# Sheet1.net
KiCad netlist of a schematic drawn in Altium Designer
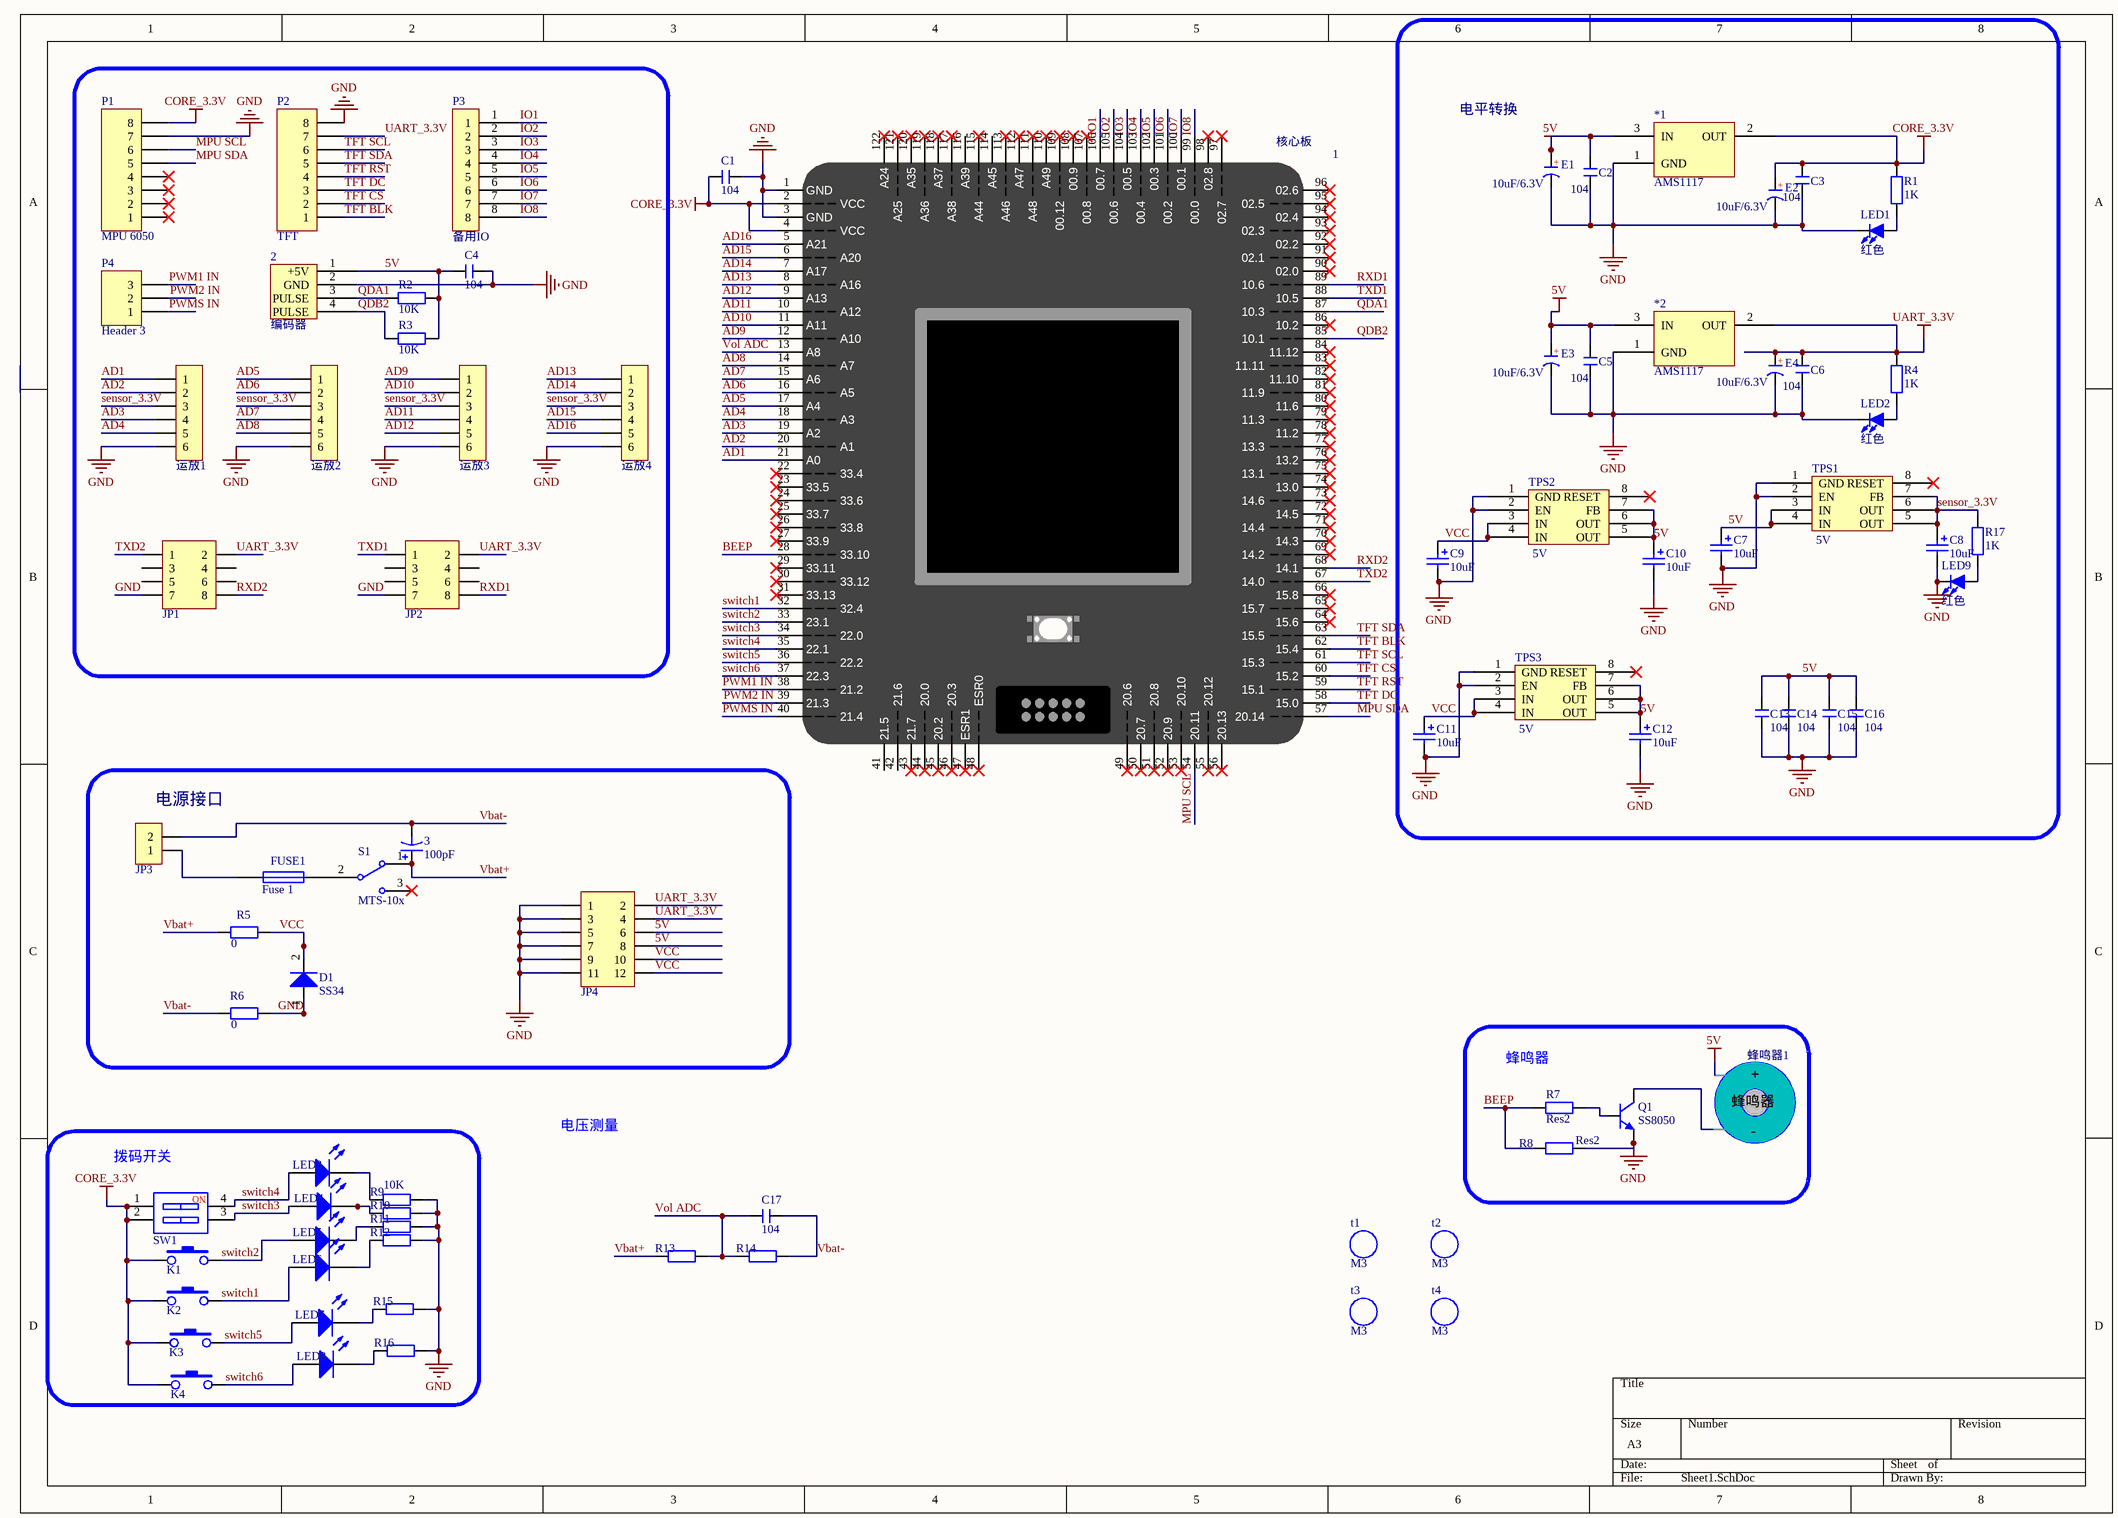
[diagram p0: Sheet1.SchDoc]

(export (version "E")
  (design (tool "Eeschema 10.0.6"))
  (components
    (comp (ref "*1") (value "AMS1117") (footprint "SOT223_M") (libsource (lib "Schlib1") (part "AMS1117")))
    (comp (ref "*2") (value "AMS1117") (footprint "SOT223_M") (libsource (lib "Schlib1") (part "AMS1117")))
    (comp (ref "1") (value "核心板") (footprint "TC264_CoreBoard") (libsource (lib "核心板") (part "Component_1")))
    (comp (ref "2") (value "编码器") (footprint "HDR1X4") (libsource (lib "我的元件库") (part "光电码盘")))
    (comp (ref "3")
      (value "100pF")
      (footprint "CAP 5.0*10*20 - BK")
      (description "Polarized Capacitor (Surface Mount)")
      (fields (field (name "Comment") "Cap Pol3") (field (name "PUBLISHER") "Altium Limited"))
      (libsource (lib "Miscellaneous Devices") (part "Cap Pol3"))
    )
    (comp (ref "C1")
      (value "104")
      (footprint "C 0603_M")
      (description "无极性贴片电容")
      (fields (field (name "版权归属") "源创客"))
      (libsource (lib "3.1   - 电阻-电容-电感") (part "C"))
    )
    (comp (ref "C2")
      (value "104")
      (footprint "C 0603_M")
      (description "无极性贴片电容")
      (fields (field (name "版权归属") "源创客"))
      (libsource (lib "3.1   - 电阻-电容-电感") (part "C"))
    )
    (comp (ref "C3")
      (value "104")
      (footprint "C 0603_M")
      (description "无极性贴片电容")
      (fields (field (name "版权归属") "源创客"))
      (libsource (lib "3.1   - 电阻-电容-电感") (part "C"))
    )
    (comp (ref "C4")
      (value "104")
      (footprint "C 0603_M")
      (description "无极性贴片电容")
      (fields (field (name "版权归属") "源创客"))
      (libsource (lib "3.1   - 电阻-电容-电感") (part "C"))
    )
    (comp (ref "C5")
      (value "104")
      (footprint "C 0603_M")
      (description "无极性贴片电容")
      (fields (field (name "版权归属") "源创客"))
      (libsource (lib "3.1   - 电阻-电容-电感") (part "C"))
    )
    (comp (ref "C6")
      (value "104")
      (footprint "C 0603_M")
      (description "无极性贴片电容")
      (fields (field (name "版权归属") "源创客"))
      (libsource (lib "3.1   - 电阻-电容-电感") (part "C"))
    )
    (comp (ref "C7")
      (value "10uF")
      (footprint "C3216")
      (description "Polarized Capacitor (Radial)")
      (fields (field (name "Comment") "10uf") (field (name "PUBLISHER") "Altium Limited"))
      (libsource (lib "SYUCT2018_2") (part "Cap Pol1"))
    )
    (comp (ref "C8")
      (value "10uF")
      (footprint "C3216")
      (description "Polarized Capacitor (Radial)")
      (fields (field (name "Comment") "10uf") (field (name "PUBLISHER") "Altium Limited"))
      (libsource (lib "SYUCT2018_2") (part "Cap Pol1"))
    )
    (comp (ref "C9")
      (value "10uF")
      (footprint "C3216")
      (description "Polarized Capacitor (Radial)")
      (fields (field (name "Comment") "10uf") (field (name "PUBLISHER") "Altium Limited"))
      (libsource (lib "SYUCT2018_2") (part "Cap Pol1"))
    )
    (comp (ref "C10")
      (value "10uF")
      (footprint "C3216")
      (description "Polarized Capacitor (Radial)")
      (fields (field (name "Comment") "10uf") (field (name "PUBLISHER") "Altium Limited"))
      (libsource (lib "SYUCT2018_2") (part "Cap Pol1"))
    )
    (comp (ref "C11")
      (value "10uF")
      (footprint "C3216")
      (description "Polarized Capacitor (Radial)")
      (fields (field (name "Comment") "10uf") (field (name "PUBLISHER") "Altium Limited"))
      (libsource (lib "SYUCT2018_2") (part "Cap Pol1"))
    )
    (comp (ref "C12")
      (value "10uF")
      (footprint "C3216")
      (description "Polarized Capacitor (Radial)")
      (fields (field (name "Comment") "10uf") (field (name "PUBLISHER") "Altium Limited"))
      (libsource (lib "SYUCT2018_2") (part "Cap Pol1"))
    )
    (comp (ref "C13")
      (value "104")
      (footprint "C 0603_M")
      (description "无极性贴片电容")
      (fields (field (name "版权归属") "源创客"))
      (libsource (lib "3.1   - 电阻-电容-电感") (part "C"))
    )
    (comp (ref "C14")
      (value "104")
      (footprint "C 0603_M")
      (description "无极性贴片电容")
      (fields (field (name "版权归属") "源创客"))
      (libsource (lib "3.1   - 电阻-电容-电感") (part "C"))
    )
    (comp (ref "C15")
      (value "104")
      (footprint "C 0603_M")
      (description "无极性贴片电容")
      (fields (field (name "版权归属") "源创客"))
      (libsource (lib "3.1   - 电阻-电容-电感") (part "C"))
    )
    (comp (ref "C16")
      (value "104")
      (footprint "C 0603_M")
      (description "无极性贴片电容")
      (fields (field (name "版权归属") "源创客"))
      (libsource (lib "3.1   - 电阻-电容-电感") (part "C"))
    )
    (comp (ref "C17")
      (value "104")
      (footprint "C 0603_M")
      (description "无极性贴片电容")
      (fields (field (name "版权归属") "源创客"))
      (libsource (lib "3.1   - 电阻-电容-电感") (part "C"))
    )
    (comp (ref "D1")
      (value "SS34")
      (footprint "SMA")
      (description "High Conductance Fast Diode")
      (fields (field (name "PUBLISHER") "Altium Limited"))
      (libsource (lib "Miscellaneous Devices") (part "Diode 1N4148"))
    )
    (comp (ref "E1")
      (value "10uF/6.3V")
      (footprint "CD A(3216)")
      (description "贴片钽电容")
      (fields (field (name "版权归属") "源创客"))
      (libsource (lib "3.1   - 电阻-电容-电感") (part "C-CD"))
    )
    (comp (ref "E2")
      (value "10uF/6.3V")
      (footprint "CD A(3216)")
      (description "贴片钽电容")
      (fields (field (name "版权归属") "源创客"))
      (libsource (lib "3.1   - 电阻-电容-电感") (part "C-CD"))
    )
    (comp (ref "E3")
      (value "10uF/6.3V")
      (footprint "CD A(3216)")
      (description "贴片钽电容")
      (fields (field (name "版权归属") "源创客"))
      (libsource (lib "3.1   - 电阻-电容-电感") (part "C-CD"))
    )
    (comp (ref "E4")
      (value "10uF/6.3V")
      (footprint "CD A(3216)")
      (description "贴片钽电容")
      (fields (field (name "版权归属") "源创客"))
      (libsource (lib "3.1   - 电阻-电容-电感") (part "C-CD"))
    )
    (comp (ref "FUSE1")
      (value "Fuse 1")
      (footprint "FU 0805")
      (description "Fuse")
      (fields (field (name "PUBLISHER") "Altium Limited"))
      (libsource (lib "Miscellaneous Devices") (part "Fuse 1"))
    )
    (comp (ref "JP1")
      (value "Header 4X2")
      (footprint "HDR2.54-LI-2x4P")
      (description "4*2P接插件")
      (fields (field (name "版权归属") "源创客"))
      (libsource (lib "4.5   - 接插件-脚距2.54") (part "Header 4X2"))
    )
    (comp (ref "JP2")
      (value "Header 4X2")
      (footprint "HDR2.54-LI-2x4P")
      (description "4*2P接插件")
      (fields (field (name "版权归属") "源创客"))
      (libsource (lib "4.5   - 接插件-脚距2.54") (part "Header 4X2"))
    )
    (comp (ref "JP3")
      (value "HDR-1X2")
      (footprint "KF301-5.0-2P")
      (description "2P接插件")
      (fields (field (name "版权归属") "源创客"))
      (libsource (lib "4.9   - 接插件-脚距5.0") (part "Header 2"))
    )
    (comp (ref "JP4")
      (value "Header 6X2")
      (footprint "HDR2.54-LI-2x6P")
      (description "6*2P接插件")
      (fields (field (name "版权归属") "源创客"))
      (libsource (lib "4.5   - 接插件-脚距2.54") (part "Header  6X2"))
    )
    (comp (ref "K1")
      (value "K2")
      (footprint "KEY-SMD1")
      (description "按键")
      (libsource (lib "PCB_Project-1.0") (part "KEY_1"))
    )
    (comp (ref "K2")
      (value "K2")
      (footprint "KEY-SMD1")
      (description "按键")
      (libsource (lib "PCB_Project-1.0") (part "KEY_1"))
    )
    (comp (ref "K3")
      (value "K2")
      (footprint "KEY-SMD1")
      (description "按键")
      (libsource (lib "PCB_Project-1.0") (part "KEY_1"))
    )
    (comp (ref "K4")
      (value "K2")
      (footprint "KEY-SMD1")
      (description "按键")
      (libsource (lib "PCB_Project-1.0") (part "KEY_1"))
    )
    (comp (ref "LED1")
      (value "红色")
      (footprint "LED 0805B")
      (description "贴片LED")
      (fields (field (name "版权归属") "源创客"))
      (libsource (lib "9.1   - LED") (part "LED-SMD"))
    )
    (comp (ref "LED2")
      (value "红色")
      (footprint "LED 0805B")
      (description "贴片LED")
      (fields (field (name "版权归属") "源创客"))
      (libsource (lib "9.1   - LED") (part "LED-SMD"))
    )
    (comp (ref "LED3")
      (value "LED4")
      (footprint "LED 0805B")
      (description "Typical RED, GREEN, YELLOW, AMBER GaAs LED")
      (fields (field (name "PUBLISHER") "Altium Limited"))
      (libsource (lib "SYUCT2018_1") (part "LED2"))
    )
    (comp (ref "LED4")
      (value "LED4")
      (footprint "LED 0805B")
      (description "Typical RED, GREEN, YELLOW, AMBER GaAs LED")
      (fields (field (name "PUBLISHER") "Altium Limited"))
      (libsource (lib "SYUCT2018_1") (part "LED2"))
    )
    (comp (ref "LED5")
      (value "LED4")
      (footprint "LED 0805B")
      (description "Typical RED, GREEN, YELLOW, AMBER GaAs LED")
      (fields (field (name "PUBLISHER") "Altium Limited"))
      (libsource (lib "SYUCT2018_1") (part "LED2"))
    )
    (comp (ref "LED6")
      (value "LED4")
      (footprint "LED 0805B")
      (description "Typical RED, GREEN, YELLOW, AMBER GaAs LED")
      (fields (field (name "PUBLISHER") "Altium Limited"))
      (libsource (lib "SYUCT2018_1") (part "LED2"))
    )
    (comp (ref "LED7")
      (value "LED4")
      (footprint "LED 0805B")
      (description "Typical RED, GREEN, YELLOW, AMBER GaAs LED")
      (fields (field (name "PUBLISHER") "Altium Limited"))
      (libsource (lib "SYUCT2018_1") (part "LED2"))
    )
    (comp (ref "LED8")
      (value "LED4")
      (footprint "LED 0805B")
      (description "Typical RED, GREEN, YELLOW, AMBER GaAs LED")
      (fields (field (name "PUBLISHER") "Altium Limited"))
      (libsource (lib "SYUCT2018_1") (part "LED2"))
    )
    (comp (ref "LED9")
      (value "红色")
      (footprint "LED 0805B")
      (description "贴片LED")
      (fields (field (name "版权归属") "源创客"))
      (libsource (lib "9.1   - LED") (part "LED-SMD"))
    )
    (comp (ref "P1")
      (value "MPU 6050")
      (footprint "HDR1X8")
      (description "Header, 8-Pin")
      (fields (field (name "PUBLISHER") "Altium Limited"))
      (libsource (lib "Miscellaneous Connectors") (part "Header 8"))
    )
    (comp (ref "P2")
      (value "TFT")
      (footprint "HDR1X8")
      (description "Header, 8-Pin")
      (fields (field (name "PUBLISHER") "Altium Limited"))
      (libsource (lib "Miscellaneous Connectors") (part "Header 8"))
    )
    (comp (ref "P3") (value "备用IO") (footprint "HDR1X8") (libsource (lib "Schlib1") (part "备用IO")))
    (comp (ref "P4")
      (value "Header 3")
      (footprint "HDR1X3")
      (description "Header, 3-Pin")
      (fields (field (name "PUBLISHER") "Altium Limited"))
      (libsource (lib "Miscellaneous Connectors") (part "Header 3"))
    )
    (comp (ref "Q1")
      (value "SS8050")
      (footprint "SOT23-3N")
      (description "高频放大-NPN型")
      (fields (field (name "版权归属") "源创客"))
      (libsource (lib "6.2   - 三极管") (part "8050-SMD"))
    )
    (comp (ref "R1")
      (value "1K")
      (footprint "R0805")
      (description "贴片电阻")
      (fields (field (name "版权归属") "源创客"))
      (libsource (lib "3.1   - 电阻-电容-电感") (part "R"))
    )
    (comp (ref "R2") (value "10K") (footprint "R0805") (libsource (lib "") (part "RES_MD_1")))
    (comp (ref "R3") (value "10K") (footprint "R0805") (libsource (lib "") (part "RES_MD_2")))
    (comp (ref "R4")
      (value "1K")
      (footprint "R0805")
      (description "贴片电阻")
      (fields (field (name "版权归属") "源创客"))
      (libsource (lib "3.1   - 电阻-电容-电感") (part "R"))
    )
    (comp (ref "R5") (value "0") (footprint "R1210") (libsource (lib "MD_分立元件自定义标准库") (part "RES_MD")))
    (comp (ref "R6") (value "0") (footprint "R1210") (libsource (lib "MD_分立元件自定义标准库") (part "RES_MD")))
    (comp (ref "R7")
      (value "Res2")
      (footprint "R0805")
      (description "Resistor")
      (fields (field (name "PUBLISHER") "Altium Limited"))
      (libsource (lib "") (part "Res2_1"))
    )
    (comp (ref "R8")
      (value "Res2")
      (footprint "R0805")
      (description "Resistor")
      (fields (field (name "PUBLISHER") "Altium Limited"))
      (libsource (lib "Miscellaneous Devices") (part "Res2"))
    )
    (comp (ref "R9")
      (value "10K")
      (footprint "R0805")
      (description "Resistor")
      (fields (field (name "PUBLISHER") "Altium Limited"))
      (libsource (lib "我的元件库") (part "电阻"))
    )
    (comp (ref "R10")
      (value "10K")
      (footprint "R0805")
      (description "Resistor")
      (fields (field (name "PUBLISHER") "Altium Limited"))
      (libsource (lib "我的元件库") (part "电阻"))
    )
    (comp (ref "R11")
      (value "10K")
      (footprint "R0805")
      (description "Resistor")
      (fields (field (name "PUBLISHER") "Altium Limited"))
      (libsource (lib "我的元件库") (part "电阻"))
    )
    (comp (ref "R12")
      (value "10K")
      (footprint "R0805")
      (description "Resistor")
      (fields (field (name "PUBLISHER") "Altium Limited"))
      (libsource (lib "我的元件库") (part "电阻"))
    )
    (comp (ref "R13")
      (value "10K")
      (footprint "R0805")
      (description "Resistor")
      (fields (field (name "PUBLISHER") "Altium Limited"))
      (libsource (lib "我的元件库") (part "电阻"))
    )
    (comp (ref "R14")
      (value "10K")
      (footprint "R0805")
      (description "Resistor")
      (fields (field (name "PUBLISHER") "Altium Limited"))
      (libsource (lib "我的元件库") (part "电阻"))
    )
    (comp (ref "R15")
      (value "10K")
      (footprint "R0805")
      (description "Resistor")
      (fields (field (name "PUBLISHER") "Altium Limited"))
      (libsource (lib "我的元件库") (part "电阻"))
    )
    (comp (ref "R16")
      (value "10K")
      (footprint "R0805")
      (description "Resistor")
      (fields (field (name "PUBLISHER") "Altium Limited"))
      (libsource (lib "我的元件库") (part "电阻"))
    )
    (comp (ref "R17")
      (value "1K")
      (footprint "R0805")
      (description "贴片电阻")
      (fields (field (name "版权归属") "源创客"))
      (libsource (lib "3.1   - 电阻-电容-电感") (part "R"))
    )
    (comp (ref "S1")
      (value "MTS-10x")
      (footprint "MTS-10x")
      (description "MTS10x系列3脚扭子开关")
      (fields (field (name "版权归属") "源创客"))
      (libsource (lib "5.1   - 按键-开关") (part "MTS-10x"))
    )
    (comp (ref "SW1")
      (value "CSW-2P")
      (footprint "CSW DIP-2P_G")
      (description "2路编码开关")
      (fields (field (name "版权归属") "源创客"))
      (libsource (lib "PCB_Project-1.0") (part "CSW-2P"))
    )
    (comp (ref "t1")
      (value "M3")
      (footprint "M3 125X200")
      (description "铜柱孔")
      (fields (field (name "版权归属") "源创客"))
      (libsource (lib "15.1 - 未分类器件") (part "M3"))
    )
    (comp (ref "t2")
      (value "M3")
      (footprint "M3 125X200")
      (description "铜柱孔")
      (fields (field (name "版权归属") "源创客"))
      (libsource (lib "15.1 - 未分类器件") (part "M3"))
    )
    (comp (ref "t3")
      (value "M3")
      (footprint "M3 125X200")
      (description "铜柱孔")
      (fields (field (name "版权归属") "源创客"))
      (libsource (lib "15.1 - 未分类器件") (part "M3"))
    )
    (comp (ref "t4")
      (value "M3")
      (footprint "M3 125X200")
      (description "铜柱孔")
      (fields (field (name "版权归属") "源创客"))
      (libsource (lib "15.1 - 未分类器件") (part "M3"))
    )
    (comp (ref "TPS1") (value "5V") (footprint "SO-8N") (libsource (lib "我的元件库") (part "TPS7350")))
    (comp (ref "TPS2") (value "5V") (footprint "SO-8N") (libsource (lib "我的元件库") (part "TPS7350")))
    (comp (ref "TPS3") (value "5V") (footprint "SO-8N") (libsource (lib "我的元件库") (part "TPS7350")))
    (comp (ref "蜂鸣器1") (value "蜂鸣器") (footprint "BELL 7.6mm") (libsource (lib "原理图") (part "蜂鸣器")))
    (comp (ref "运放1")
      (value "HDR-1X6")
      (footprint "XH2.54-LI-6P")
      (description "6P接插件")
      (libsource (lib "5.1 - 接插件-脚距1.27") (part "Header 6"))
    )
    (comp (ref "运放2")
      (value "HDR-1X6")
      (footprint "XH2.54-LI-6P")
      (description "6P接插件")
      (libsource (lib "5.1 - 接插件-脚距1.27") (part "Header 6"))
    )
    (comp (ref "运放3")
      (value "HDR-1X6")
      (footprint "XH2.54-LI-6P")
      (description "6P接插件")
      (libsource (lib "5.1 - 接插件-脚距1.27") (part "Header 6"))
    )
    (comp (ref "运放4")
      (value "HDR-1X6")
      (footprint "XH2.54-LI-6P")
      (description "6P接插件")
      (libsource (lib "5.1 - 接插件-脚距1.27") (part "Header 6"))
    )
  )
  (nets
    (net (code "1") (name "/AD1") (class "Default")
      (node (ref "1") (pin "21") (pinfunction "A0_21") (pintype "passive"))
      (node (ref "运放1") (pin "1") (pinfunction "1_1") (pintype "passive"))
    )
    (net (code "2") (name "/AD2") (class "Default")
      (node (ref "1") (pin "20") (pinfunction "A1_20") (pintype "passive"))
      (node (ref "运放1") (pin "2") (pinfunction "2_2") (pintype "passive"))
    )
    (net (code "3") (name "/AD3") (class "Default")
      (node (ref "1") (pin "19") (pinfunction "A2_19") (pintype "passive"))
      (node (ref "运放1") (pin "4") (pinfunction "4_4") (pintype "passive"))
    )
    (net (code "4") (name "/AD4") (class "Default")
      (node (ref "1") (pin "18") (pinfunction "A3_18") (pintype "passive"))
      (node (ref "运放1") (pin "5") (pinfunction "5_5") (pintype "passive"))
    )
    (net (code "5") (name "/AD5") (class "Default")
      (node (ref "1") (pin "17") (pinfunction "A4_17") (pintype "passive"))
      (node (ref "运放2") (pin "1") (pinfunction "1_1") (pintype "passive"))
    )
    (net (code "6") (name "/AD6") (class "Default")
      (node (ref "1") (pin "16") (pinfunction "A5_16") (pintype "passive"))
      (node (ref "运放2") (pin "2") (pinfunction "2_2") (pintype "passive"))
    )
    (net (code "7") (name "/AD7") (class "Default")
      (node (ref "1") (pin "15") (pinfunction "A6_15") (pintype "passive"))
      (node (ref "运放2") (pin "4") (pinfunction "4_4") (pintype "passive"))
    )
    (net (code "8") (name "/AD8") (class "Default")
      (node (ref "1") (pin "14") (pinfunction "A7_14") (pintype "passive"))
      (node (ref "运放2") (pin "5") (pinfunction "5_5") (pintype "passive"))
    )
    (net (code "9") (name "/AD9") (class "Default")
      (node (ref "1") (pin "12") (pinfunction "A10_12") (pintype "passive"))
      (node (ref "运放3") (pin "1") (pinfunction "1_1") (pintype "passive"))
    )
    (net (code "10") (name "/AD10") (class "Default")
      (node (ref "1") (pin "11") (pinfunction "A11_11") (pintype "passive"))
      (node (ref "运放3") (pin "2") (pinfunction "2_2") (pintype "passive"))
    )
    (net (code "11") (name "/AD11") (class "Default")
      (node (ref "1") (pin "10") (pinfunction "A12_10") (pintype "passive"))
      (node (ref "运放3") (pin "4") (pinfunction "4_4") (pintype "passive"))
    )
    (net (code "12") (name "/AD12") (class "Default")
      (node (ref "1") (pin "9") (pinfunction "A13_9") (pintype "passive"))
      (node (ref "运放3") (pin "5") (pinfunction "5_5") (pintype "passive"))
    )
    (net (code "13") (name "/AD13") (class "Default")
      (node (ref "1") (pin "8") (pinfunction "A16_8") (pintype "passive"))
      (node (ref "运放4") (pin "1") (pinfunction "1_1") (pintype "passive"))
    )
    (net (code "14") (name "/AD14") (class "Default")
      (node (ref "1") (pin "7") (pinfunction "A17_7") (pintype "passive"))
      (node (ref "运放4") (pin "2") (pinfunction "2_2") (pintype "passive"))
    )
    (net (code "15") (name "/AD15") (class "Default")
      (node (ref "1") (pin "6") (pinfunction "A20_6") (pintype "passive"))
      (node (ref "运放4") (pin "4") (pinfunction "4_4") (pintype "passive"))
    )
    (net (code "16") (name "/AD16") (class "Default")
      (node (ref "1") (pin "5") (pinfunction "A21_5") (pintype "passive"))
      (node (ref "运放4") (pin "5") (pinfunction "5_5") (pintype "passive"))
    )
    (net (code "17") (name "/BEEP") (class "Default")
      (node (ref "1") (pin "28") (pinfunction "33.10_28") (pintype "passive"))
      (node (ref "R7") (pin "2") (pinfunction "2_2") (pintype "passive"))
      (node (ref "R8") (pin "1") (pinfunction "1_1") (pintype "passive"))
    )
    (net (code "18") (name "/IO1") (class "Default")
      (node (ref "1") (pin "106") (pinfunction "00.7_106") (pintype "passive"))
      (node (ref "P3") (pin "1") (pinfunction "1_1") (pintype "passive"))
    )
    (net (code "19") (name "/IO2") (class "Default")
      (node (ref "1") (pin "105") (pinfunction "00.6_105") (pintype "passive"))
      (node (ref "P3") (pin "2") (pinfunction "2_2") (pintype "passive"))
    )
    (net (code "20") (name "/IO3") (class "Default")
      (node (ref "1") (pin "104") (pinfunction "00.5_104") (pintype "passive"))
      (node (ref "P3") (pin "3") (pinfunction "3_3") (pintype "passive"))
    )
    (net (code "21") (name "/IO4") (class "Default")
      (node (ref "1") (pin "103") (pinfunction "00.4_103") (pintype "passive"))
      (node (ref "P3") (pin "4") (pinfunction "4_4") (pintype "passive"))
    )
    (net (code "22") (name "/IO5") (class "Default")
      (node (ref "1") (pin "102") (pinfunction "00.3_102") (pintype "passive"))
      (node (ref "P3") (pin "5") (pinfunction "5_5") (pintype "passive"))
    )
    (net (code "23") (name "/IO6") (class "Default")
      (node (ref "1") (pin "101") (pinfunction "00.2_101") (pintype "passive"))
      (node (ref "P3") (pin "6") (pinfunction "6_6") (pintype "passive"))
    )
    (net (code "24") (name "/IO7") (class "Default")
      (node (ref "1") (pin "100") (pinfunction "00.1_100") (pintype "passive"))
      (node (ref "P3") (pin "7") (pinfunction "7_7") (pintype "passive"))
    )
    (net (code "25") (name "/IO8") (class "Default")
      (node (ref "1") (pin "99") (pinfunction "00.0_99") (pintype "passive"))
      (node (ref "P3") (pin "8") (pinfunction "8_8") (pintype "passive"))
    )
    (net (code "26") (name "/MPU SCL") (class "Default")
      (node (ref "1") (pin "54") (pinfunction "20.11_54") (pintype "passive"))
      (node (ref "P1") (pin "6") (pinfunction "6_6") (pintype "passive"))
    )
    (net (code "27") (name "/MPU SDA") (class "Default")
      (node (ref "1") (pin "57") (pinfunction "20.14_57") (pintype "passive"))
      (node (ref "P1") (pin "5") (pinfunction "5_5") (pintype "passive"))
    )
    (net (code "28") (name "/PWM1 IN") (class "Default")
      (node (ref "1") (pin "38") (pinfunction "21.2_38") (pintype "passive"))
      (node (ref "P4") (pin "3") (pinfunction "3_3") (pintype "passive"))
    )
    (net (code "29") (name "/PWM2 IN") (class "Default")
      (node (ref "1") (pin "39") (pinfunction "21.3_39") (pintype "passive"))
      (node (ref "P4") (pin "2") (pinfunction "2_2") (pintype "passive"))
    )
    (net (code "30") (name "/PWMS IN") (class "Default")
      (node (ref "1") (pin "40") (pinfunction "21.4_40") (pintype "passive"))
      (node (ref "P4") (pin "1") (pinfunction "1_1") (pintype "passive"))
    )
    (net (code "31") (name "/QDA1") (class "Default")
      (node (ref "1") (pin "87") (pinfunction "10.3_87") (pintype "passive"))
      (node (ref "2") (pin "3") (pinfunction "PULSE_3") (pintype "passive"))
      (node (ref "R2") (pin "1") (pinfunction "1_1") (pintype "passive"))
    )
    (net (code "32") (name "/QDB2") (class "Default")
      (node (ref "1") (pin "85") (pinfunction "10.1_85") (pintype "passive"))
      (node (ref "2") (pin "4") (pinfunction "PULSE_4") (pintype "passive"))
      (node (ref "R3") (pin "2") (pinfunction "2_2") (pintype "passive"))
    )
    (net (code "33") (name "/RXD1") (class "Default")
      (node (ref "1") (pin "89") (pinfunction "10.6_89") (pintype "passive"))
      (node (ref "JP2") (pin "8") (pinfunction "8_8") (pintype "passive"))
    )
    (net (code "34") (name "/RXD2") (class "Default")
      (node (ref "1") (pin "68") (pinfunction "14.1_68") (pintype "passive"))
      (node (ref "JP1") (pin "8") (pinfunction "8_8") (pintype "passive"))
    )
    (net (code "35") (name "/TFT BLK") (class "Default")
      (node (ref "1") (pin "62") (pinfunction "15.4_62") (pintype "passive"))
      (node (ref "P2") (pin "1") (pinfunction "1_1") (pintype "passive"))
    )
    (net (code "36") (name "/TFT CS") (class "Default")
      (node (ref "1") (pin "60") (pinfunction "15.2_60") (pintype "passive"))
      (node (ref "P2") (pin "2") (pinfunction "2_2") (pintype "passive"))
    )
    (net (code "37") (name "/TFT DC") (class "Default")
      (node (ref "1") (pin "58") (pinfunction "15.0_58") (pintype "passive"))
      (node (ref "P2") (pin "3") (pinfunction "3_3") (pintype "passive"))
    )
    (net (code "38") (name "/TFT RST") (class "Default")
      (node (ref "1") (pin "59") (pinfunction "15.1_59") (pintype "passive"))
      (node (ref "P2") (pin "4") (pinfunction "4_4") (pintype "passive"))
    )
    (net (code "39") (name "/TFT SCL") (class "Default")
      (node (ref "1") (pin "61") (pinfunction "15.3_61") (pintype "passive"))
      (node (ref "P2") (pin "6") (pinfunction "6_6") (pintype "passive"))
    )
    (net (code "40") (name "/TFT SDA") (class "Default")
      (node (ref "1") (pin "63") (pinfunction "15.5_63") (pintype "passive"))
      (node (ref "P2") (pin "5") (pinfunction "5_5") (pintype "passive"))
    )
    (net (code "41") (name "/TXD1") (class "Default")
      (node (ref "1") (pin "88") (pinfunction "10.5_88") (pintype "passive"))
      (node (ref "JP2") (pin "1") (pinfunction "1_1") (pintype "passive"))
    )
    (net (code "42") (name "/TXD2") (class "Default")
      (node (ref "1") (pin "67") (pinfunction "14.0_67") (pintype "passive"))
      (node (ref "JP1") (pin "1") (pinfunction "1_1") (pintype "passive"))
    )
    (net (code "43") (name "/VCC") (class "Default")
      (node (ref "C11") (pin "1") (pinfunction "1_1") (pintype "passive"))
      (node (ref "C9") (pin "1") (pinfunction "1_1") (pintype "passive"))
      (node (ref "D1") (pin "2") (pinfunction "K_2") (pintype "passive"))
      (node (ref "JP4") (pin "10") (pinfunction "10_10") (pintype "passive"))
      (node (ref "JP4") (pin "12") (pinfunction "12_12") (pintype "passive"))
      (node (ref "R5") (pin "1") (pinfunction "vcc_1") (pintype "passive"))
      (node (ref "TPS2") (pin "3") (pinfunction "IN_3") (pintype "passive"))
      (node (ref "TPS2") (pin "4") (pinfunction "IN_4") (pintype "passive"))
      (node (ref "TPS3") (pin "3") (pinfunction "IN_3") (pintype "passive"))
      (node (ref "TPS3") (pin "4") (pinfunction "IN_4") (pintype "passive"))
    )
    (net (code "44") (name "/Vbat+") (class "Default")
      (node (ref "3") (pin "1") (pinfunction "1_1") (pintype "passive"))
      (node (ref "R13") (pin "1") (pinfunction "1_1") (pintype "passive"))
      (node (ref "R5") (pin "2") (pinfunction "2_2") (pintype "passive"))
      (node (ref "S1") (pin "1") (pinfunction "1_1") (pintype "passive"))
    )
    (net (code "45") (name "/Vbat-") (class "Default")
      (node (ref "3") (pin "2") (pinfunction "2_2") (pintype "passive"))
      (node (ref "C17") (pin "1") (pinfunction "1_1") (pintype "passive"))
      (node (ref "JP3") (pin "1") (pinfunction "2_1") (pintype "passive"))
      (node (ref "R14") (pin "2") (pinfunction "2_2") (pintype "passive"))
      (node (ref "R6") (pin "2") (pinfunction "2_2") (pintype "passive"))
    )
    (net (code "46") (name "/Vol ADC") (class "Default")
      (node (ref "1") (pin "13") (pinfunction "A8_13") (pintype "passive"))
      (node (ref "C17") (pin "2") (pinfunction "2_2") (pintype "passive"))
      (node (ref "R13") (pin "2") (pinfunction "2_2") (pintype "passive"))
      (node (ref "R14") (pin "1") (pinfunction "1_1") (pintype "passive"))
    )
    (net (code "47") (name "/sensor_3.3V") (class "Default")
      (node (ref "C8") (pin "1") (pinfunction "1_1") (pintype "passive"))
      (node (ref "R17") (pin "2") (pinfunction "2_2") (pintype "passive"))
      (node (ref "TPS1") (pin "5") (pinfunction "OUT_5") (pintype "passive"))
      (node (ref "TPS1") (pin "6") (pinfunction "OUT_6") (pintype "passive"))
      (node (ref "TPS1") (pin "7") (pinfunction "FB_7") (pintype "passive"))
      (node (ref "运放1") (pin "3") (pinfunction "3_3") (pintype "passive"))
      (node (ref "运放2") (pin "3") (pinfunction "3_3") (pintype "passive"))
      (node (ref "运放3") (pin "3") (pinfunction "3_3") (pintype "passive"))
      (node (ref "运放4") (pin "3") (pinfunction "3_3") (pintype "passive"))
    )
    (net (code "48") (name "/switch1") (class "Default")
      (node (ref "1") (pin "32") (pinfunction "32.4_32") (pintype "passive"))
      (node (ref "K2") (pin "2") (pinfunction "2_2") (pintype "passive"))
      (node (ref "LED6") (pin "1") (pinfunction "A_1") (pintype "passive"))
    )
    (net (code "49") (name "/switch2") (class "Default")
      (node (ref "1") (pin "33") (pinfunction "23.1_33") (pintype "passive"))
      (node (ref "K1") (pin "2") (pinfunction "2_2") (pintype "passive"))
      (node (ref "LED5") (pin "1") (pinfunction "A_1") (pintype "passive"))
    )
    (net (code "50") (name "/switch3") (class "Default")
      (node (ref "1") (pin "34") (pinfunction "22.0_34") (pintype "passive"))
      (node (ref "LED4") (pin "1") (pinfunction "A_1") (pintype "passive"))
      (node (ref "SW1") (pin "3") (pinfunction "3_3") (pintype "passive"))
    )
    (net (code "51") (name "/switch4") (class "Default")
      (node (ref "1") (pin "35") (pinfunction "22.1_35") (pintype "passive"))
      (node (ref "LED3") (pin "1") (pinfunction "A_1") (pintype "passive"))
      (node (ref "SW1") (pin "4") (pinfunction "4_4") (pintype "passive"))
    )
    (net (code "52") (name "/switch5") (class "Default")
      (node (ref "1") (pin "36") (pinfunction "22.2_36") (pintype "passive"))
      (node (ref "K3") (pin "2") (pinfunction "2_2") (pintype "passive"))
      (node (ref "LED7") (pin "1") (pinfunction "A_1") (pintype "passive"))
    )
    (net (code "53") (name "/switch6") (class "Default")
      (node (ref "1") (pin "37") (pinfunction "22.3_37") (pintype "passive"))
      (node (ref "K4") (pin "2") (pinfunction "2_2") (pintype "passive"))
      (node (ref "LED8") (pin "1") (pinfunction "A_1") (pintype "passive"))
    )
    (net (code "54") (name "5V") (class "Default")
      (node (ref "*1") (pin "3") (pinfunction "IN_3") (pintype "passive"))
      (node (ref "*2") (pin "3") (pinfunction "IN_3") (pintype "passive"))
      (node (ref "2") (pin "1") (pinfunction "+5V_1") (pintype "passive"))
      (node (ref "C10") (pin "1") (pinfunction "1_1") (pintype "passive"))
      (node (ref "C12") (pin "1") (pinfunction "1_1") (pintype "passive"))
      (node (ref "C13") (pin "1") (pinfunction "1_1") (pintype "passive"))
      (node (ref "C14") (pin "1") (pinfunction "1_1") (pintype "passive"))
      (node (ref "C15") (pin "1") (pinfunction "1_1") (pintype "passive"))
      (node (ref "C16") (pin "1") (pinfunction "1_1") (pintype "passive"))
      (node (ref "C2") (pin "2") (pinfunction "2_2") (pintype "passive"))
      (node (ref "C4") (pin "2") (pinfunction "2_2") (pintype "passive"))
      (node (ref "C5") (pin "2") (pinfunction "2_2") (pintype "passive"))
      (node (ref "C7") (pin "1") (pinfunction "1_1") (pintype "passive"))
      (node (ref "E1") (pin "1") (pinfunction "A_1") (pintype "passive"))
      (node (ref "E3") (pin "1") (pinfunction "A_1") (pintype "passive"))
      (node (ref "JP4") (pin "6") (pinfunction "6_6") (pintype "passive"))
      (node (ref "JP4") (pin "8") (pinfunction "8_8") (pintype "passive"))
      (node (ref "R2") (pin "2") (pinfunction "2_2") (pintype "passive"))
      (node (ref "R3") (pin "1") (pinfunction "1_1") (pintype "passive"))
      (node (ref "TPS1") (pin "3") (pinfunction "IN_3") (pintype "passive"))
      (node (ref "TPS1") (pin "4") (pinfunction "IN_4") (pintype "passive"))
      (node (ref "TPS2") (pin "5") (pinfunction "OUT_5") (pintype "passive"))
      (node (ref "TPS2") (pin "6") (pinfunction "OUT_6") (pintype "passive"))
      (node (ref "TPS2") (pin "7") (pinfunction "FB_7") (pintype "passive"))
      (node (ref "TPS3") (pin "5") (pinfunction "OUT_5") (pintype "passive"))
      (node (ref "TPS3") (pin "6") (pinfunction "OUT_6") (pintype "passive"))
      (node (ref "TPS3") (pin "7") (pinfunction "FB_7") (pintype "passive"))
      (node (ref "蜂鸣器1") (pin "1") (pinfunction "1_1") (pintype "passive"))
    )
    (net (code "55") (name "CORE_3.3V") (class "Default")
      (node (ref "*1") (pin "2") (pinfunction "OUT_2") (pintype "passive"))
      (node (ref "1") (pin "2") (pinfunction "VCC_2") (pintype "passive"))
      (node (ref "1") (pin "4") (pinfunction "VCC_4") (pintype "passive"))
      (node (ref "C1") (pin "2") (pinfunction "2_2") (pintype "passive"))
      (node (ref "C3") (pin "2") (pinfunction "2_2") (pintype "passive"))
      (node (ref "E2") (pin "1") (pinfunction "A_1") (pintype "passive"))
      (node (ref "K1") (pin "1") (pinfunction "1_1") (pintype "passive"))
      (node (ref "K2") (pin "1") (pinfunction "1_1") (pintype "passive"))
      (node (ref "K3") (pin "1") (pinfunction "1_1") (pintype "passive"))
      (node (ref "K4") (pin "1") (pinfunction "1_1") (pintype "passive"))
      (node (ref "P1") (pin "8") (pinfunction "8_8") (pintype "passive"))
      (node (ref "R1") (pin "2") (pinfunction "2_2") (pintype "passive"))
      (node (ref "SW1") (pin "1") (pinfunction "1_1") (pintype "passive"))
      (node (ref "SW1") (pin "2") (pinfunction "2_2") (pintype "passive"))
    )
    (net (code "56") (name "GND") (class "Default")
      (node (ref "*1") (pin "1") (pinfunction "GND_1") (pintype "passive"))
      (node (ref "*2") (pin "1") (pinfunction "GND_1") (pintype "passive"))
      (node (ref "1") (pin "1") (pinfunction "GND_1") (pintype "passive"))
      (node (ref "1") (pin "3") (pinfunction "GND_3") (pintype "passive"))
      (node (ref "2") (pin "2") (pinfunction "GND_2") (pintype "passive"))
      (node (ref "C1") (pin "1") (pinfunction "1_1") (pintype "passive"))
      (node (ref "C10") (pin "2") (pinfunction "2_2") (pintype "passive"))
      (node (ref "C11") (pin "2") (pinfunction "2_2") (pintype "passive"))
      (node (ref "C12") (pin "2") (pinfunction "2_2") (pintype "passive"))
      (node (ref "C13") (pin "2") (pinfunction "2_2") (pintype "passive"))
      (node (ref "C14") (pin "2") (pinfunction "2_2") (pintype "passive"))
      (node (ref "C15") (pin "2") (pinfunction "2_2") (pintype "passive"))
      (node (ref "C16") (pin "2") (pinfunction "2_2") (pintype "passive"))
      (node (ref "C2") (pin "1") (pinfunction "1_1") (pintype "passive"))
      (node (ref "C3") (pin "1") (pinfunction "1_1") (pintype "passive"))
      (node (ref "C4") (pin "1") (pinfunction "1_1") (pintype "passive"))
      (node (ref "C5") (pin "1") (pinfunction "1_1") (pintype "passive"))
      (node (ref "C6") (pin "1") (pinfunction "1_1") (pintype "passive"))
      (node (ref "C7") (pin "2") (pinfunction "2_2") (pintype "passive"))
      (node (ref "C8") (pin "2") (pinfunction "2_2") (pintype "passive"))
      (node (ref "C9") (pin "2") (pinfunction "2_2") (pintype "passive"))
      (node (ref "D1") (pin "1") (pinfunction "A_1") (pintype "passive"))
      (node (ref "E1") (pin "2") (pinfunction "K_2") (pintype "passive"))
      (node (ref "E2") (pin "2") (pinfunction "K_2") (pintype "passive"))
      (node (ref "E3") (pin "2") (pinfunction "K_2") (pintype "passive"))
      (node (ref "E4") (pin "2") (pinfunction "K_2") (pintype "passive"))
      (node (ref "JP1") (pin "7") (pinfunction "7_7") (pintype "passive"))
      (node (ref "JP2") (pin "7") (pinfunction "7_7") (pintype "passive"))
      (node (ref "JP4") (pin "1") (pinfunction "1_1") (pintype "passive"))
      (node (ref "JP4") (pin "11") (pinfunction "11_11") (pintype "passive"))
      (node (ref "JP4") (pin "3") (pinfunction "3_3") (pintype "passive"))
      (node (ref "JP4") (pin "5") (pinfunction "5_5") (pintype "passive"))
      (node (ref "JP4") (pin "7") (pinfunction "7_7") (pintype "passive"))
      (node (ref "JP4") (pin "9") (pinfunction "9_9") (pintype "passive"))
      (node (ref "LED1") (pin "2") (pinfunction "K_2") (pintype "passive"))
      (node (ref "LED2") (pin "2") (pinfunction "K_2") (pintype "passive"))
      (node (ref "LED9") (pin "2") (pinfunction "K_2") (pintype "passive"))
      (node (ref "P1") (pin "7") (pinfunction "7_7") (pintype "passive"))
      (node (ref "P2") (pin "8") (pinfunction "8_8") (pintype "passive"))
      (node (ref "Q1") (pin "2") (pinfunction "E_2") (pintype "passive"))
      (node (ref "R10") (pin "2") (pinfunction "2_2") (pintype "passive"))
      (node (ref "R11") (pin "2") (pinfunction "2_2") (pintype "passive"))
      (node (ref "R12") (pin "2") (pinfunction "2_2") (pintype "passive"))
      (node (ref "R15") (pin "2") (pinfunction "2_2") (pintype "passive"))
      (node (ref "R16") (pin "2") (pinfunction "2_2") (pintype "passive"))
      (node (ref "R6") (pin "1") (pinfunction "vcc_1") (pintype "passive"))
      (node (ref "R8") (pin "2") (pinfunction "2_2") (pintype "passive"))
      (node (ref "R9") (pin "2") (pinfunction "2_2") (pintype "passive"))
      (node (ref "TPS1") (pin "1") (pinfunction "GND_1") (pintype "passive"))
      (node (ref "TPS1") (pin "2") (pinfunction "EN_2") (pintype "passive"))
      (node (ref "TPS2") (pin "1") (pinfunction "GND_1") (pintype "passive"))
      (node (ref "TPS2") (pin "2") (pinfunction "EN_2") (pintype "passive"))
      (node (ref "TPS3") (pin "1") (pinfunction "GND_1") (pintype "passive"))
      (node (ref "TPS3") (pin "2") (pinfunction "EN_2") (pintype "passive"))
      (node (ref "运放1") (pin "6") (pinfunction "6_6") (pintype "passive"))
      (node (ref "运放2") (pin "6") (pinfunction "6_6") (pintype "passive"))
      (node (ref "运放3") (pin "6") (pinfunction "6_6") (pintype "passive"))
      (node (ref "运放4") (pin "6") (pinfunction "6_6") (pintype "passive"))
    )
    (net (code "57") (name "Net-(FUSE1-Pad2)") (class "Default")
      (node (ref "FUSE1") (pin "2") (pinfunction "2_2") (pintype "passive"))
      (node (ref "S1") (pin "2") (pinfunction "2_2") (pintype "passive"))
    )
    (net (code "58") (name "Net-(JP3-1)") (class "Default")
      (node (ref "FUSE1") (pin "1") (pinfunction "1_1") (pintype "passive"))
      (node (ref "JP3") (pin "2") (pinfunction "1_2") (pintype "passive"))
    )
    (net (code "59") (name "Net-(LED1-A)") (class "Default")
      (node (ref "LED1") (pin "1") (pinfunction "A_1") (pintype "passive"))
      (node (ref "R1") (pin "1") (pinfunction "1_1") (pintype "passive"))
    )
    (net (code "60") (name "Net-(LED2-A)") (class "Default")
      (node (ref "LED2") (pin "1") (pinfunction "A_1") (pintype "passive"))
      (node (ref "R4") (pin "1") (pinfunction "1_1") (pintype "passive"))
    )
    (net (code "61") (name "Net-(LED3-K)") (class "Default")
      (node (ref "LED3") (pin "2") (pinfunction "K_2") (pintype "passive"))
      (node (ref "R9") (pin "1") (pinfunction "1_1") (pintype "passive"))
    )
    (net (code "62") (name "Net-(LED4-K)") (class "Default")
      (node (ref "LED4") (pin "2") (pinfunction "K_2") (pintype "passive"))
      (node (ref "R10") (pin "1") (pinfunction "1_1") (pintype "passive"))
    )
    (net (code "63") (name "Net-(LED5-K)") (class "Default")
      (node (ref "LED5") (pin "2") (pinfunction "K_2") (pintype "passive"))
      (node (ref "R11") (pin "1") (pinfunction "1_1") (pintype "passive"))
    )
    (net (code "64") (name "Net-(LED6-K)") (class "Default")
      (node (ref "LED6") (pin "2") (pinfunction "K_2") (pintype "passive"))
      (node (ref "R12") (pin "1") (pinfunction "1_1") (pintype "passive"))
    )
    (net (code "65") (name "Net-(LED7-K)") (class "Default")
      (node (ref "LED7") (pin "2") (pinfunction "K_2") (pintype "passive"))
      (node (ref "R15") (pin "1") (pinfunction "1_1") (pintype "passive"))
    )
    (net (code "66") (name "Net-(LED8-K)") (class "Default")
      (node (ref "LED8") (pin "2") (pinfunction "K_2") (pintype "passive"))
      (node (ref "R16") (pin "1") (pinfunction "1_1") (pintype "passive"))
    )
    (net (code "67") (name "Net-(LED9-A)") (class "Default")
      (node (ref "LED9") (pin "1") (pinfunction "A_1") (pintype "passive"))
      (node (ref "R17") (pin "1") (pinfunction "1_1") (pintype "passive"))
    )
    (net (code "68") (name "Net-(Q1-B)") (class "Default")
      (node (ref "Q1") (pin "1") (pinfunction "B_1") (pintype "passive"))
      (node (ref "R7") (pin "1") (pinfunction "1_1") (pintype "passive"))
    )
    (net (code "69") (name "Net-(Q1-C)") (class "Default")
      (node (ref "Q1") (pin "3") (pinfunction "C_3") (pintype "passive"))
      (node (ref "蜂鸣器1") (pin "2") (pinfunction "2_2") (pintype "passive"))
    )
    (net (code "70") (name "UART_3.3V") (class "Default")
      (node (ref "*2") (pin "2") (pinfunction "OUT_2") (pintype "passive"))
      (node (ref "C6") (pin "2") (pinfunction "2_2") (pintype "passive"))
      (node (ref "E4") (pin "1") (pinfunction "A_1") (pintype "passive"))
      (node (ref "JP1") (pin "2") (pinfunction "2_2") (pintype "passive"))
      (node (ref "JP2") (pin "2") (pinfunction "2_2") (pintype "passive"))
      (node (ref "JP4") (pin "2") (pinfunction "2_2") (pintype "passive"))
      (node (ref "JP4") (pin "4") (pinfunction "4_4") (pintype "passive"))
      (node (ref "P2") (pin "7") (pinfunction "7_7") (pintype "passive"))
      (node (ref "R4") (pin "2") (pinfunction "2_2") (pintype "passive"))
    )
    (net (code "71") (name "unconnected-(1-00.8-Pad107)") (class "Default")
      (node (ref "1") (pin "107") (pinfunction "00.8_107") (pintype "passive+no_connect"))
    )
    (net (code "72") (name "unconnected-(1-00.9-Pad108)") (class "Default")
      (node (ref "1") (pin "108") (pinfunction "00.9_108") (pintype "passive+no_connect"))
    )
    (net (code "73") (name "unconnected-(1-00.12-Pad109)") (class "Default")
      (node (ref "1") (pin "109") (pinfunction "00.12_109") (pintype "passive+no_connect"))
    )
    (net (code "74") (name "unconnected-(1-02.0-Pad90)") (class "Default")
      (node (ref "1") (pin "90") (pinfunction "02.0_90") (pintype "passive+no_connect"))
    )
    (net (code "75") (name "unconnected-(1-02.1-Pad91)") (class "Default")
      (node (ref "1") (pin "91") (pinfunction "02.1_91") (pintype "passive+no_connect"))
    )
    (net (code "76") (name "unconnected-(1-02.2-Pad92)") (class "Default")
      (node (ref "1") (pin "92") (pinfunction "02.2_92") (pintype "passive+no_connect"))
    )
    (net (code "77") (name "unconnected-(1-02.3-Pad93)") (class "Default")
      (node (ref "1") (pin "93") (pinfunction "02.3_93") (pintype "passive+no_connect"))
    )
    (net (code "78") (name "unconnected-(1-02.4-Pad94)") (class "Default")
      (node (ref "1") (pin "94") (pinfunction "02.4_94") (pintype "passive+no_connect"))
    )
    (net (code "79") (name "unconnected-(1-02.5-Pad95)") (class "Default")
      (node (ref "1") (pin "95") (pinfunction "02.5_95") (pintype "passive+no_connect"))
    )
    (net (code "80") (name "unconnected-(1-02.6-Pad96)") (class "Default")
      (node (ref "1") (pin "96") (pinfunction "02.6_96") (pintype "passive+no_connect"))
    )
    (net (code "81") (name "unconnected-(1-02.7-Pad97)") (class "Default")
      (node (ref "1") (pin "97") (pinfunction "02.7_97") (pintype "passive+no_connect"))
    )
    (net (code "82") (name "unconnected-(1-02.8-Pad98)") (class "Default")
      (node (ref "1") (pin "98") (pinfunction "02.8_98") (pintype "passive+no_connect"))
    )
    (net (code "83") (name "unconnected-(1-10.2-Pad86)") (class "Default")
      (node (ref "1") (pin "86") (pinfunction "10.2_86") (pintype "passive+no_connect"))
    )
    (net (code "84") (name "unconnected-(1-11.2-Pad78)") (class "Default")
      (node (ref "1") (pin "78") (pinfunction "11.2_78") (pintype "passive+no_connect"))
    )
    (net (code "85") (name "unconnected-(1-11.3-Pad79)") (class "Default")
      (node (ref "1") (pin "79") (pinfunction "11.3_79") (pintype "passive+no_connect"))
    )
    (net (code "86") (name "unconnected-(1-11.6-Pad80)") (class "Default")
      (node (ref "1") (pin "80") (pinfunction "11.6_80") (pintype "passive+no_connect"))
    )
    (net (code "87") (name "unconnected-(1-11.9-Pad81)") (class "Default")
      (node (ref "1") (pin "81") (pinfunction "11.9_81") (pintype "passive+no_connect"))
    )
    (net (code "88") (name "unconnected-(1-11.10-Pad82)") (class "Default")
      (node (ref "1") (pin "82") (pinfunction "11.10_82") (pintype "passive+no_connect"))
    )
    (net (code "89") (name "unconnected-(1-11.11-Pad83)") (class "Default")
      (node (ref "1") (pin "83") (pinfunction "11.11_83") (pintype "passive+no_connect"))
    )
    (net (code "90") (name "unconnected-(1-11.12-Pad84)") (class "Default")
      (node (ref "1") (pin "84") (pinfunction "11.12_84") (pintype "passive+no_connect"))
    )
    (net (code "91") (name "unconnected-(1-13.0-Pad74)") (class "Default")
      (node (ref "1") (pin "74") (pinfunction "13.0_74") (pintype "passive+no_connect"))
    )
    (net (code "92") (name "unconnected-(1-13.1-Pad75)") (class "Default")
      (node (ref "1") (pin "75") (pinfunction "13.1_75") (pintype "passive+no_connect"))
    )
    (net (code "93") (name "unconnected-(1-13.2-Pad76)") (class "Default")
      (node (ref "1") (pin "76") (pinfunction "13.2_76") (pintype "passive+no_connect"))
    )
    (net (code "94") (name "unconnected-(1-13.3-Pad77)") (class "Default")
      (node (ref "1") (pin "77") (pinfunction "13.3_77") (pintype "passive+no_connect"))
    )
    (net (code "95") (name "unconnected-(1-14.2-Pad69)") (class "Default")
      (node (ref "1") (pin "69") (pinfunction "14.2_69") (pintype "passive+no_connect"))
    )
    (net (code "96") (name "unconnected-(1-14.3-Pad70)") (class "Default")
      (node (ref "1") (pin "70") (pinfunction "14.3_70") (pintype "passive+no_connect"))
    )
    (net (code "97") (name "unconnected-(1-14.4-Pad71)") (class "Default")
      (node (ref "1") (pin "71") (pinfunction "14.4_71") (pintype "passive+no_connect"))
    )
    (net (code "98") (name "unconnected-(1-14.5-Pad72)") (class "Default")
      (node (ref "1") (pin "72") (pinfunction "14.5_72") (pintype "passive+no_connect"))
    )
    (net (code "99") (name "unconnected-(1-14.6-Pad73)") (class "Default")
      (node (ref "1") (pin "73") (pinfunction "14.6_73") (pintype "passive+no_connect"))
    )
    (net (code "100") (name "unconnected-(1-15.6-Pad64)") (class "Default")
      (node (ref "1") (pin "64") (pinfunction "15.6_64") (pintype "passive+no_connect"))
    )
    (net (code "101") (name "unconnected-(1-15.7-Pad65)") (class "Default")
      (node (ref "1") (pin "65") (pinfunction "15.7_65") (pintype "passive+no_connect"))
    )
    (net (code "102") (name "unconnected-(1-15.8-Pad66)") (class "Default")
      (node (ref "1") (pin "66") (pinfunction "15.8_66") (pintype "passive+no_connect"))
    )
    (net (code "103") (name "unconnected-(1-20.0-Pad44)") (class "Default")
      (node (ref "1") (pin "44") (pinfunction "20.0_44") (pintype "passive+no_connect"))
    )
    (net (code "104") (name "unconnected-(1-20.2-Pad45)") (class "Default")
      (node (ref "1") (pin "45") (pinfunction "20.2_45") (pintype "passive+no_connect"))
    )
    (net (code "105") (name "unconnected-(1-20.3-Pad46)") (class "Default")
      (node (ref "1") (pin "46") (pinfunction "20.3_46") (pintype "passive+no_connect"))
    )
    (net (code "106") (name "unconnected-(1-20.6-Pad49)") (class "Default")
      (node (ref "1") (pin "49") (pinfunction "20.6_49") (pintype "passive+no_connect"))
    )
    (net (code "107") (name "unconnected-(1-20.7-Pad50)") (class "Default")
      (node (ref "1") (pin "50") (pinfunction "20.7_50") (pintype "passive+no_connect"))
    )
    (net (code "108") (name "unconnected-(1-20.8-Pad51)") (class "Default")
      (node (ref "1") (pin "51") (pinfunction "20.8_51") (pintype "passive+no_connect"))
    )
    (net (code "109") (name "unconnected-(1-20.9-Pad52)") (class "Default")
      (node (ref "1") (pin "52") (pinfunction "20.9_52") (pintype "passive+no_connect"))
    )
    (net (code "110") (name "unconnected-(1-20.10-Pad53)") (class "Default")
      (node (ref "1") (pin "53") (pinfunction "20.10_53") (pintype "passive+no_connect"))
    )
    (net (code "111") (name "unconnected-(1-20.12-Pad55)") (class "Default")
      (node (ref "1") (pin "55") (pinfunction "20.12_55") (pintype "passive+no_connect"))
    )
    (net (code "112") (name "unconnected-(1-20.13-Pad56)") (class "Default")
      (node (ref "1") (pin "56") (pinfunction "20.13_56") (pintype "passive+no_connect"))
    )
    (net (code "113") (name "unconnected-(1-21.5-Pad41)") (class "Default")
      (node (ref "1") (pin "41") (pinfunction "21.5_41") (pintype "passive"))
    )
    (net (code "114") (name "unconnected-(1-21.6-Pad42)") (class "Default")
      (node (ref "1") (pin "42") (pinfunction "21.6_42") (pintype "passive"))
    )
    (net (code "115") (name "unconnected-(1-21.7-Pad43)") (class "Default")
      (node (ref "1") (pin "43") (pinfunction "21.7_43") (pintype "passive+no_connect"))
    )
    (net (code "116") (name "unconnected-(1-33.4-Pad22)") (class "Default")
      (node (ref "1") (pin "22") (pinfunction "33.4_22") (pintype "passive+no_connect"))
    )
    (net (code "117") (name "unconnected-(1-33.5-Pad23)") (class "Default")
      (node (ref "1") (pin "23") (pinfunction "33.5_23") (pintype "passive+no_connect"))
    )
    (net (code "118") (name "unconnected-(1-33.6-Pad24)") (class "Default")
      (node (ref "1") (pin "24") (pinfunction "33.6_24") (pintype "passive+no_connect"))
    )
    (net (code "119") (name "unconnected-(1-33.7-Pad25)") (class "Default")
      (node (ref "1") (pin "25") (pinfunction "33.7_25") (pintype "passive+no_connect"))
    )
    (net (code "120") (name "unconnected-(1-33.8-Pad26)") (class "Default")
      (node (ref "1") (pin "26") (pinfunction "33.8_26") (pintype "passive+no_connect"))
    )
    (net (code "121") (name "unconnected-(1-33.9-Pad27)") (class "Default")
      (node (ref "1") (pin "27") (pinfunction "33.9_27") (pintype "passive+no_connect"))
    )
    (net (code "122") (name "unconnected-(1-33.11-Pad29)") (class "Default")
      (node (ref "1") (pin "29") (pinfunction "33.11_29") (pintype "passive+no_connect"))
    )
    (net (code "123") (name "unconnected-(1-33.12-Pad30)") (class "Default")
      (node (ref "1") (pin "30") (pinfunction "33.12_30") (pintype "passive+no_connect"))
    )
    (net (code "124") (name "unconnected-(1-33.13-Pad31)") (class "Default")
      (node (ref "1") (pin "31") (pinfunction "33.13_31") (pintype "passive+no_connect"))
    )
    (net (code "125") (name "unconnected-(1-A24-Pad122)") (class "Default")
      (node (ref "1") (pin "122") (pinfunction "A24_122") (pintype "passive+no_connect"))
    )
    (net (code "126") (name "unconnected-(1-A25-Pad121)") (class "Default")
      (node (ref "1") (pin "121") (pinfunction "A25_121") (pintype "passive+no_connect"))
    )
    (net (code "127") (name "unconnected-(1-A35-Pad120)") (class "Default")
      (node (ref "1") (pin "120") (pinfunction "A35_120") (pintype "passive+no_connect"))
    )
    (net (code "128") (name "unconnected-(1-A36-Pad119)") (class "Default")
      (node (ref "1") (pin "119") (pinfunction "A36_119") (pintype "passive+no_connect"))
    )
    (net (code "129") (name "unconnected-(1-A37-Pad118)") (class "Default")
      (node (ref "1") (pin "118") (pinfunction "A37_118") (pintype "passive+no_connect"))
    )
    (net (code "130") (name "unconnected-(1-A38-Pad117)") (class "Default")
      (node (ref "1") (pin "117") (pinfunction "A38_117") (pintype "passive+no_connect"))
    )
    (net (code "131") (name "unconnected-(1-A39-Pad116)") (class "Default")
      (node (ref "1") (pin "116") (pinfunction "A39_116") (pintype "passive"))
    )
    (net (code "132") (name "unconnected-(1-A44-Pad115)") (class "Default")
      (node (ref "1") (pin "115") (pinfunction "A44_115") (pintype "passive+no_connect"))
    )
    (net (code "133") (name "unconnected-(1-A45-Pad114)") (class "Default")
      (node (ref "1") (pin "114") (pinfunction "A45_114") (pintype "passive"))
    )
    (net (code "134") (name "unconnected-(1-A46-Pad113)") (class "Default")
      (node (ref "1") (pin "113") (pinfunction "A46_113") (pintype "passive+no_connect"))
    )
    (net (code "135") (name "unconnected-(1-A47-Pad112)") (class "Default")
      (node (ref "1") (pin "112") (pinfunction "A47_112") (pintype "passive+no_connect"))
    )
    (net (code "136") (name "unconnected-(1-A48-Pad111)") (class "Default")
      (node (ref "1") (pin "111") (pinfunction "A48_111") (pintype "passive+no_connect"))
    )
    (net (code "137") (name "unconnected-(1-A49-Pad110)") (class "Default")
      (node (ref "1") (pin "110") (pinfunction "A49_110") (pintype "passive+no_connect"))
    )
    (net (code "138") (name "unconnected-(1-ESR0-Pad48)") (class "Default")
      (node (ref "1") (pin "48") (pinfunction "ESR0_48") (pintype "passive+no_connect"))
    )
    (net (code "139") (name "unconnected-(1-ESR1-Pad47)") (class "Default")
      (node (ref "1") (pin "47") (pinfunction "ESR1_47") (pintype "passive+no_connect"))
    )
    (net (code "140") (name "unconnected-(JP1-Pad3)") (class "Default")
      (node (ref "JP1") (pin "3") (pinfunction "3_3") (pintype "passive"))
    )
    (net (code "141") (name "unconnected-(JP1-Pad4)") (class "Default")
      (node (ref "JP1") (pin "4") (pinfunction "4_4") (pintype "passive"))
    )
    (net (code "142") (name "unconnected-(JP1-Pad5)") (class "Default")
      (node (ref "JP1") (pin "5") (pinfunction "5_5") (pintype "passive"))
    )
    (net (code "143") (name "unconnected-(JP1-Pad6)") (class "Default")
      (node (ref "JP1") (pin "6") (pinfunction "6_6") (pintype "passive"))
    )
    (net (code "144") (name "unconnected-(JP2-Pad3)") (class "Default")
      (node (ref "JP2") (pin "3") (pinfunction "3_3") (pintype "passive"))
    )
    (net (code "145") (name "unconnected-(JP2-Pad4)") (class "Default")
      (node (ref "JP2") (pin "4") (pinfunction "4_4") (pintype "passive"))
    )
    (net (code "146") (name "unconnected-(JP2-Pad5)") (class "Default")
      (node (ref "JP2") (pin "5") (pinfunction "5_5") (pintype "passive"))
    )
    (net (code "147") (name "unconnected-(JP2-Pad6)") (class "Default")
      (node (ref "JP2") (pin "6") (pinfunction "6_6") (pintype "passive"))
    )
    (net (code "148") (name "unconnected-(P1-Pad1)") (class "Default")
      (node (ref "P1") (pin "1") (pinfunction "1_1") (pintype "passive+no_connect"))
    )
    (net (code "149") (name "unconnected-(P1-Pad2)") (class "Default")
      (node (ref "P1") (pin "2") (pinfunction "2_2") (pintype "passive+no_connect"))
    )
    (net (code "150") (name "unconnected-(P1-Pad3)") (class "Default")
      (node (ref "P1") (pin "3") (pinfunction "3_3") (pintype "passive+no_connect"))
    )
    (net (code "151") (name "unconnected-(P1-Pad4)") (class "Default")
      (node (ref "P1") (pin "4") (pinfunction "4_4") (pintype "passive+no_connect"))
    )
    (net (code "152") (name "unconnected-(S1-Pad3)") (class "Default")
      (node (ref "S1") (pin "3") (pinfunction "3_3") (pintype "passive+no_connect"))
    )
    (net (code "153") (name "unconnected-(TPS1-RESET-Pad8)") (class "Default")
      (node (ref "TPS1") (pin "8") (pinfunction "RESET_8") (pintype "passive+no_connect"))
    )
    (net (code "154") (name "unconnected-(TPS2-RESET-Pad8)") (class "Default")
      (node (ref "TPS2") (pin "8") (pinfunction "RESET_8") (pintype "passive+no_connect"))
    )
    (net (code "155") (name "unconnected-(TPS3-RESET-Pad8)") (class "Default")
      (node (ref "TPS3") (pin "8") (pinfunction "RESET_8") (pintype "passive+no_connect"))
    )
  )
)
